# AVR-Timer_smd.net
KiCad netlist of a schematic drawn in EAGLE
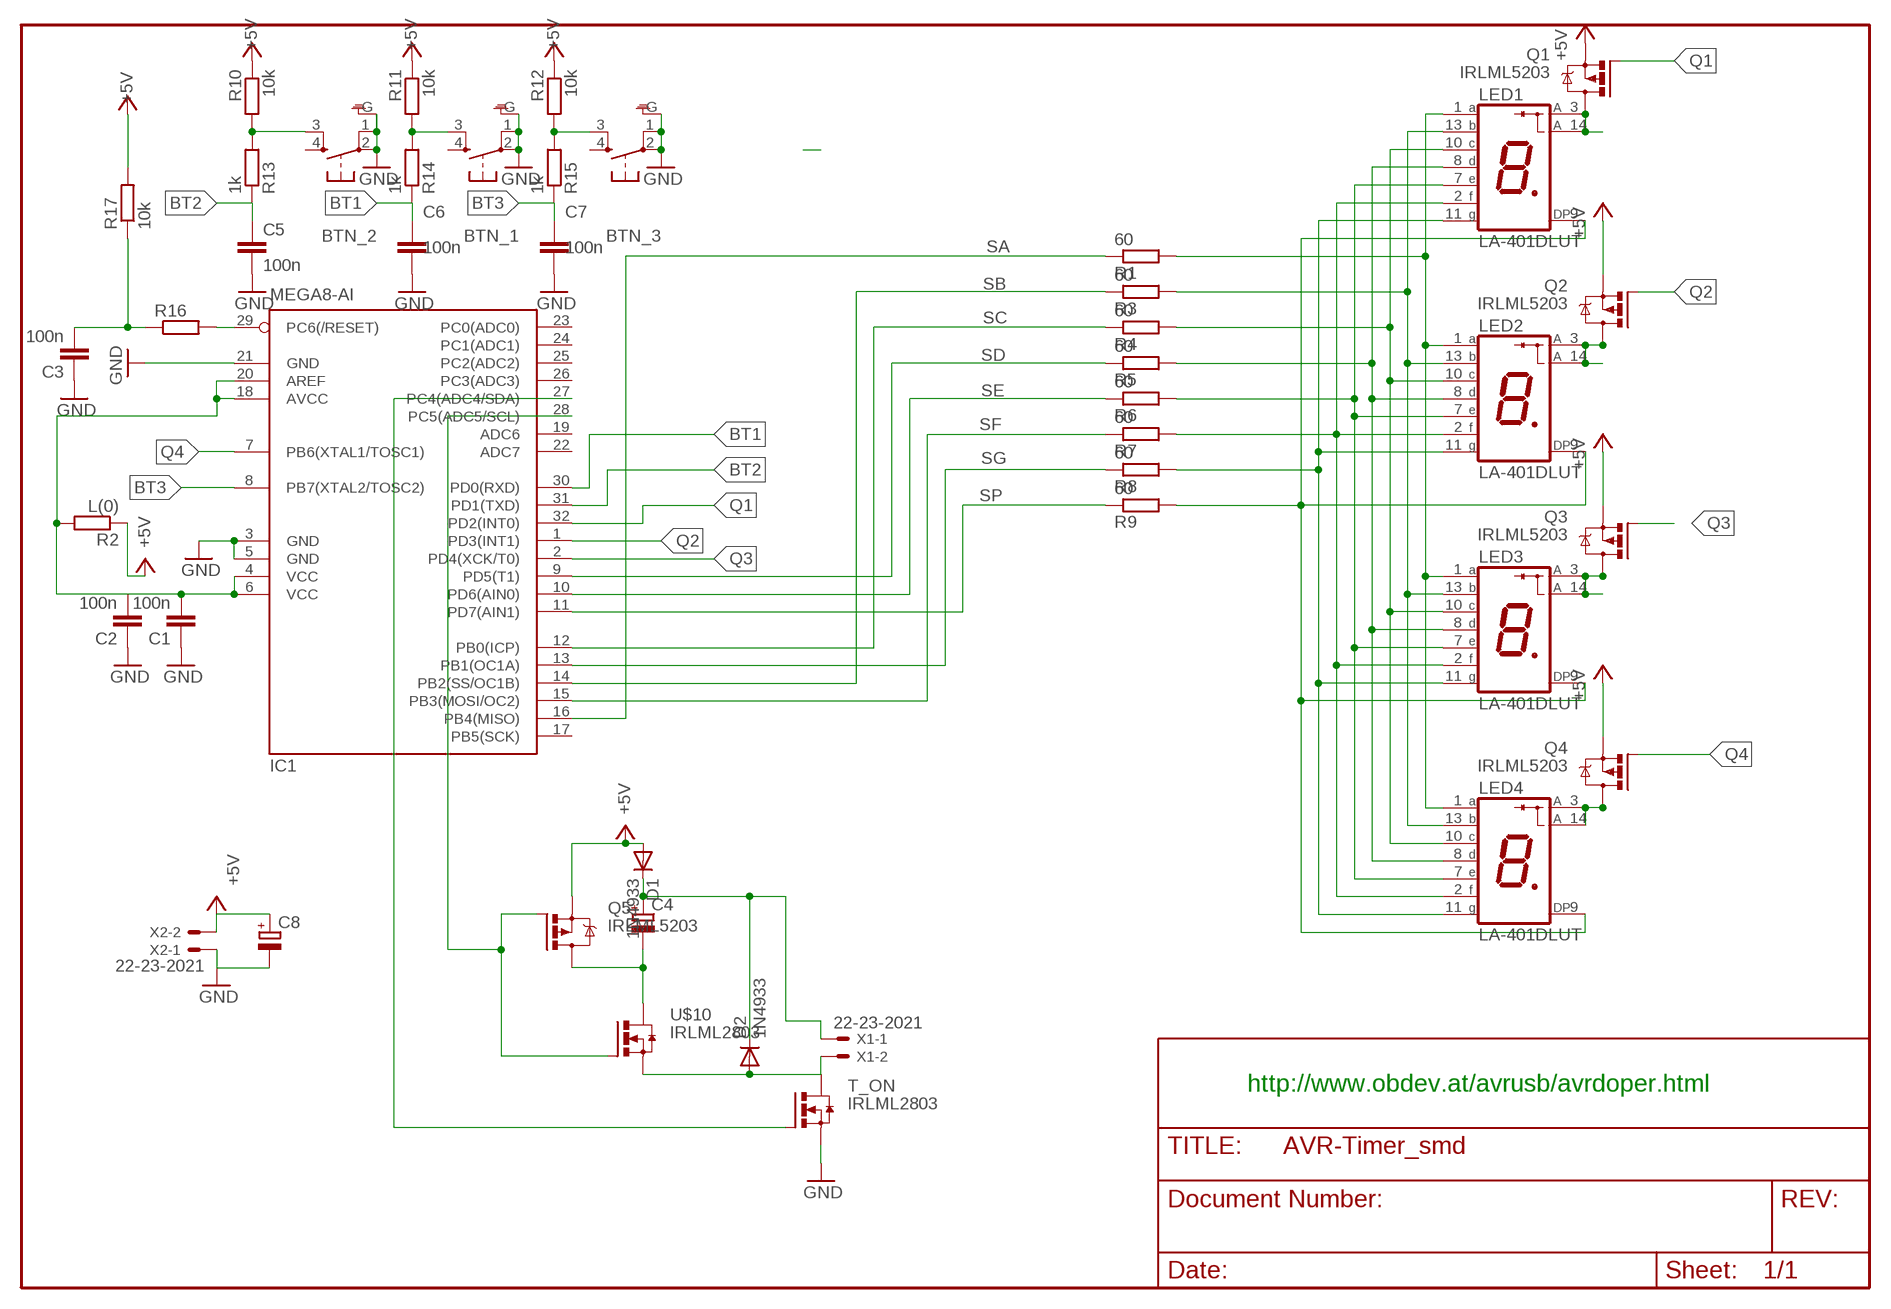
[diagram p0: schematic, sheet 1]

(export (version "E")
  (design (tool "Eeschema 10.0.6"))
  (components
    (comp (ref "BTN_1")
      (value "10-XXG")
      (footprint "eagle-import:B3F-10XXG")
      (libsource (lib "eagle-import") (part "10-XXG"))
    )
    (comp (ref "BTN_2")
      (value "10-XXG")
      (footprint "eagle-import:B3F-10XXG")
      (libsource (lib "eagle-import") (part "10-XXG"))
    )
    (comp (ref "BTN_3")
      (value "10-XXG")
      (footprint "eagle-import:B3F-10XXG")
      (libsource (lib "eagle-import") (part "10-XXG"))
    )
    (comp (ref "C1")
      (value "100n")
      (footprint "eagle-import:C0805K")
      (libsource (lib "eagle-import") (part "C-EUC0805K"))
    )
    (comp (ref "C2")
      (value "100n")
      (footprint "eagle-import:C0805K")
      (libsource (lib "eagle-import") (part "C-EUC0805K"))
    )
    (comp (ref "C3")
      (value "100n")
      (footprint "eagle-import:C0805K")
      (libsource (lib "eagle-import") (part "C-EUC0805K"))
    )
    (comp (ref "C4")
      (value "CPOL-EUE5-8.5")
      (footprint "eagle-import:E5-8,5")
      (libsource (lib "eagle-import") (part "CPOL-EUE5-8.5"))
    )
    (comp (ref "C5")
      (value "100n")
      (footprint "eagle-import:C0805K")
      (libsource (lib "eagle-import") (part "C-EUC0805K"))
    )
    (comp (ref "C6")
      (value "100n")
      (footprint "eagle-import:C0805K")
      (libsource (lib "eagle-import") (part "C-EUC0805K"))
    )
    (comp (ref "C7")
      (value "100n")
      (footprint "eagle-import:C0805K")
      (libsource (lib "eagle-import") (part "C-EUC0805K"))
    )
    (comp (ref "C8")
      (value "CPOL-EUE5-8.5")
      (footprint "eagle-import:E5-8,5")
      (libsource (lib "eagle-import") (part "CPOL-EUE5-8.5"))
    )
    (comp (ref "D1")
      (value "1N4933")
      (footprint "eagle-import:DO41-10")
      (libsource (lib "eagle-import") (part "1N4933"))
    )
    (comp (ref "D2")
      (value "1N4933")
      (footprint "eagle-import:DO41-10")
      (libsource (lib "eagle-import") (part "1N4933"))
    )
    (comp (ref "IC1")
      (value "MEGA8-AI")
      (footprint "eagle-import:TQFP32-08")
      (libsource (lib "eagle-import") (part "MEGA8-AI"))
    )
    (comp (ref "LED1")
      (value "LA-401DLUT")
      (footprint "eagle-import:MY_LUT")
      (libsource (lib "eagle-import") (part "LA-401DLUT"))
    )
    (comp (ref "LED2")
      (value "LA-401DLUT")
      (footprint "eagle-import:MY_LUT")
      (libsource (lib "eagle-import") (part "LA-401DLUT"))
    )
    (comp (ref "LED3")
      (value "LA-401DLUT")
      (footprint "eagle-import:MY_LUT")
      (libsource (lib "eagle-import") (part "LA-401DLUT"))
    )
    (comp (ref "LED4")
      (value "LA-401DLUT")
      (footprint "eagle-import:MY_LUT")
      (libsource (lib "eagle-import") (part "LA-401DLUT"))
    )
    (comp (ref "Q1")
      (value "IRLML5203")
      (footprint "eagle-import:MICRO3")
      (libsource (lib "eagle-import") (part "IRLML5203"))
    )
    (comp (ref "Q2")
      (value "IRLML5203")
      (footprint "eagle-import:MICRO3")
      (libsource (lib "eagle-import") (part "IRLML5203"))
    )
    (comp (ref "Q3")
      (value "IRLML5203")
      (footprint "eagle-import:MICRO3")
      (libsource (lib "eagle-import") (part "IRLML5203"))
    )
    (comp (ref "Q4")
      (value "IRLML5203")
      (footprint "eagle-import:MICRO3")
      (libsource (lib "eagle-import") (part "IRLML5203"))
    )
    (comp (ref "Q5")
      (value "IRLML5203")
      (footprint "eagle-import:MICRO3")
      (libsource (lib "eagle-import") (part "IRLML5203"))
    )
    (comp (ref "R1")
      (value "60")
      (footprint "eagle-import:M0805")
      (libsource (lib "eagle-import") (part "R-EU_M0805"))
    )
    (comp (ref "R2")
      (value "L(0)")
      (footprint "eagle-import:M1206")
      (libsource (lib "eagle-import") (part "R-EU_M1206"))
    )
    (comp (ref "R3")
      (value "60")
      (footprint "eagle-import:M0805")
      (libsource (lib "eagle-import") (part "R-EU_M0805"))
    )
    (comp (ref "R4")
      (value "60")
      (footprint "eagle-import:M0805")
      (libsource (lib "eagle-import") (part "R-EU_M0805"))
    )
    (comp (ref "R5")
      (value "60")
      (footprint "eagle-import:M0805")
      (libsource (lib "eagle-import") (part "R-EU_M0805"))
    )
    (comp (ref "R6")
      (value "60")
      (footprint "eagle-import:M0805")
      (libsource (lib "eagle-import") (part "R-EU_M0805"))
    )
    (comp (ref "R7")
      (value "60")
      (footprint "eagle-import:M0805")
      (libsource (lib "eagle-import") (part "R-EU_M0805"))
    )
    (comp (ref "R8")
      (value "60")
      (footprint "eagle-import:M0805")
      (libsource (lib "eagle-import") (part "R-EU_M0805"))
    )
    (comp (ref "R9")
      (value "60")
      (footprint "eagle-import:M0805")
      (libsource (lib "eagle-import") (part "R-EU_M0805"))
    )
    (comp (ref "R10")
      (value "10k")
      (footprint "eagle-import:M0805")
      (libsource (lib "eagle-import") (part "R-EU_M0805"))
    )
    (comp (ref "R11")
      (value "10k")
      (footprint "eagle-import:M0805")
      (libsource (lib "eagle-import") (part "R-EU_M0805"))
    )
    (comp (ref "R12")
      (value "10k")
      (footprint "eagle-import:M0805")
      (libsource (lib "eagle-import") (part "R-EU_M0805"))
    )
    (comp (ref "R13")
      (value "1k")
      (footprint "eagle-import:M0805")
      (libsource (lib "eagle-import") (part "R-EU_M0805"))
    )
    (comp (ref "R14")
      (value "1k")
      (footprint "eagle-import:M0805")
      (libsource (lib "eagle-import") (part "R-EU_M0805"))
    )
    (comp (ref "R15")
      (value "1k")
      (footprint "eagle-import:M0805")
      (libsource (lib "eagle-import") (part "R-EU_M0805"))
    )
    (comp (ref "R16")
      (value "R-EU_M1206")
      (footprint "eagle-import:M1206")
      (libsource (lib "eagle-import") (part "R-EU_M1206"))
    )
    (comp (ref "R17")
      (value "10k")
      (footprint "eagle-import:M1206")
      (libsource (lib "eagle-import") (part "R-EU_M1206"))
    )
    (comp (ref "T_ON")
      (value "IRLML2803")
      (footprint "eagle-import:SUPER-SOT3")
      (libsource (lib "eagle-import") (part "IRLML2803"))
    )
    (comp (ref "U$10")
      (value "IRLML2803")
      (footprint "eagle-import:SUPER-SOT3")
      (libsource (lib "eagle-import") (part "IRLML2803"))
    )
    (comp (ref "X1")
      (value "22-23-2021")
      (footprint "eagle-import:22-23-2021")
      (fields (field (name "MF") "MOLEX"))
      (libsource (lib "eagle-import") (part "22-23-2021"))
    )
    (comp (ref "X2")
      (value "22-23-2021")
      (footprint "eagle-import:22-23-2021")
      (fields
        (field (name "MF") "MOLEX")
        (field (name "MF_1") "MOLEX")
        (field (name "MPN") "22-23-2021")
        (field (name "OC_FARNELL") "1462926")
        (field (name "OC_NEWARK") "25C3832")
      )
      (libsource (lib "eagle-import") (part "22-23-2021"))
    )
  )
  (nets
    (net (code "1") (name "+5V") (class "Default")
      (node (ref "C8") (pin "+") (pinfunction "+_+") (pintype "passive"))
      (node (ref "D1") (pin "A") (pinfunction "A_A") (pintype "passive"))
      (node (ref "Q1") (pin "2") (pinfunction "S_2") (pintype "passive"))
      (node (ref "Q2") (pin "2") (pinfunction "S_2") (pintype "passive"))
      (node (ref "Q3") (pin "2") (pinfunction "S_2") (pintype "passive"))
      (node (ref "Q4") (pin "2") (pinfunction "S_2") (pintype "passive"))
      (node (ref "Q5") (pin "2") (pinfunction "S_2") (pintype "passive"))
      (node (ref "R10") (pin "1") (pinfunction "1_1") (pintype "passive"))
      (node (ref "R11") (pin "1") (pinfunction "1_1") (pintype "passive"))
      (node (ref "R12") (pin "1") (pinfunction "1_1") (pintype "passive"))
      (node (ref "R17") (pin "2") (pinfunction "2_2") (pintype "passive"))
      (node (ref "R2") (pin "1") (pinfunction "1_1") (pintype "passive"))
      (node (ref "X2") (pin "2") (pinfunction "S_2") (pintype "passive"))
    )
    (net (code "2") (name "/SA") (class "Default")
      (node (ref "IC1") (pin "16") (pinfunction "PB4(MISO)_16") (pintype "bidirectional"))
      (node (ref "R1") (pin "1") (pinfunction "1_1") (pintype "passive"))
    )
    (net (code "3") (name "/SB") (class "Default")
      (node (ref "IC1") (pin "14") (pinfunction "PB2(SS/OC1B)_14") (pintype "bidirectional"))
      (node (ref "R3") (pin "1") (pinfunction "1_1") (pintype "passive"))
    )
    (net (code "4") (name "/SC") (class "Default")
      (node (ref "IC1") (pin "12") (pinfunction "PB0(ICP)_12") (pintype "bidirectional"))
      (node (ref "R4") (pin "1") (pinfunction "1_1") (pintype "passive"))
    )
    (net (code "5") (name "/SD") (class "Default")
      (node (ref "IC1") (pin "9") (pinfunction "PD5(T1)_9") (pintype "bidirectional"))
      (node (ref "R5") (pin "1") (pinfunction "1_1") (pintype "passive"))
    )
    (net (code "6") (name "/SE") (class "Default")
      (node (ref "IC1") (pin "10") (pinfunction "PD6(AIN0)_10") (pintype "bidirectional"))
      (node (ref "R6") (pin "1") (pinfunction "1_1") (pintype "passive"))
    )
    (net (code "7") (name "/SF") (class "Default")
      (node (ref "IC1") (pin "15") (pinfunction "PB3(MOSI/OC2)_15") (pintype "bidirectional"))
      (node (ref "R7") (pin "1") (pinfunction "1_1") (pintype "passive"))
    )
    (net (code "8") (name "/SG") (class "Default")
      (node (ref "IC1") (pin "13") (pinfunction "PB1(OC1A)_13") (pintype "bidirectional"))
      (node (ref "R8") (pin "1") (pinfunction "1_1") (pintype "passive"))
    )
    (net (code "9") (name "/SP") (class "Default")
      (node (ref "IC1") (pin "11") (pinfunction "PD7(AIN1)_11") (pintype "bidirectional"))
      (node (ref "R9") (pin "1") (pinfunction "1_1") (pintype "passive"))
    )
    (net (code "10") (name "BT1") (class "Default")
      (node (ref "C6") (pin "1") (pinfunction "1_1") (pintype "passive"))
      (node (ref "IC1") (pin "30") (pinfunction "PD0(RXD)_30") (pintype "bidirectional"))
      (node (ref "R14") (pin "1") (pinfunction "1_1") (pintype "passive"))
    )
    (net (code "11") (name "BT2") (class "Default")
      (node (ref "C5") (pin "1") (pinfunction "1_1") (pintype "passive"))
      (node (ref "IC1") (pin "31") (pinfunction "PD1(TXD)_31") (pintype "bidirectional"))
      (node (ref "R13") (pin "1") (pinfunction "1_1") (pintype "passive"))
    )
    (net (code "12") (name "BT3") (class "Default")
      (node (ref "C7") (pin "1") (pinfunction "1_1") (pintype "passive"))
      (node (ref "IC1") (pin "8") (pinfunction "PB7(XTAL2/TOSC2)_8") (pintype "bidirectional"))
      (node (ref "R15") (pin "1") (pinfunction "1_1") (pintype "passive"))
    )
    (net (code "13") (name "GND") (class "Default")
      (node (ref "BTN_1") (pin "1") (pinfunction "P1_1") (pintype "passive"))
      (node (ref "BTN_1") (pin "2") (pinfunction "P_2") (pintype "passive"))
      (node (ref "BTN_1") (pin "G") (pinfunction "GND_G") (pintype "power_in"))
      (node (ref "BTN_2") (pin "1") (pinfunction "P1_1") (pintype "passive"))
      (node (ref "BTN_2") (pin "2") (pinfunction "P_2") (pintype "passive"))
      (node (ref "BTN_2") (pin "G") (pinfunction "GND_G") (pintype "power_in"))
      (node (ref "BTN_3") (pin "1") (pinfunction "P1_1") (pintype "passive"))
      (node (ref "BTN_3") (pin "2") (pinfunction "P_2") (pintype "passive"))
      (node (ref "BTN_3") (pin "G") (pinfunction "GND_G") (pintype "power_in"))
      (node (ref "C1") (pin "1") (pinfunction "1_1") (pintype "passive"))
      (node (ref "C2") (pin "1") (pinfunction "1_1") (pintype "passive"))
      (node (ref "C3") (pin "1") (pinfunction "1_1") (pintype "passive"))
      (node (ref "C5") (pin "2") (pinfunction "2_2") (pintype "passive"))
      (node (ref "C6") (pin "2") (pinfunction "2_2") (pintype "passive"))
      (node (ref "C7") (pin "2") (pinfunction "2_2") (pintype "passive"))
      (node (ref "C8") (pin "-") (pinfunction "-_-") (pintype "passive"))
      (node (ref "IC1") (pin "21") (pinfunction "GND_21") (pintype "power_in"))
      (node (ref "IC1") (pin "3") (pinfunction "GND_3") (pintype "power_in"))
      (node (ref "IC1") (pin "5") (pinfunction "GND_5") (pintype "power_in"))
      (node (ref "T_ON") (pin "2") (pinfunction "S_2") (pintype "passive"))
      (node (ref "X2") (pin "1") (pinfunction "S_1") (pintype "passive"))
    )
    (net (code "14") (name "Net-(BTN_1-S1)") (class "Default")
      (node (ref "BTN_1") (pin "3") (pinfunction "S1_3") (pintype "passive"))
      (node (ref "R11") (pin "2") (pinfunction "2_2") (pintype "passive"))
      (node (ref "R14") (pin "2") (pinfunction "2_2") (pintype "passive"))
    )
    (net (code "15") (name "Net-(BTN_2-S1)") (class "Default")
      (node (ref "BTN_2") (pin "3") (pinfunction "S1_3") (pintype "passive"))
      (node (ref "R10") (pin "2") (pinfunction "2_2") (pintype "passive"))
      (node (ref "R13") (pin "2") (pinfunction "2_2") (pintype "passive"))
    )
    (net (code "16") (name "Net-(BTN_3-S1)") (class "Default")
      (node (ref "BTN_3") (pin "3") (pinfunction "S1_3") (pintype "passive"))
      (node (ref "R12") (pin "2") (pinfunction "2_2") (pintype "passive"))
      (node (ref "R15") (pin "2") (pinfunction "2_2") (pintype "passive"))
    )
    (net (code "17") (name "Net-(C3-Pad2)") (class "Default")
      (node (ref "C3") (pin "2") (pinfunction "2_2") (pintype "passive"))
      (node (ref "R16") (pin "1") (pinfunction "1_1") (pintype "passive"))
      (node (ref "R17") (pin "1") (pinfunction "1_1") (pintype "passive"))
    )
    (net (code "18") (name "Net-(IC1-AREF)") (class "Default")
      (node (ref "C1") (pin "2") (pinfunction "2_2") (pintype "passive"))
      (node (ref "C2") (pin "2") (pinfunction "2_2") (pintype "passive"))
      (node (ref "IC1") (pin "18") (pinfunction "AVCC_18") (pintype "power_in"))
      (node (ref "IC1") (pin "20") (pinfunction "AREF_20") (pintype "passive"))
      (node (ref "IC1") (pin "4") (pinfunction "VCC_4") (pintype "power_in"))
      (node (ref "IC1") (pin "6") (pinfunction "VCC_6") (pintype "power_in"))
      (node (ref "R2") (pin "2") (pinfunction "2_2") (pintype "passive"))
    )
    (net (code "19") (name "Net-(IC1-PC4(ADC4{slash}SDA))") (class "Default")
      (node (ref "IC1") (pin "27") (pinfunction "PC4(ADC4/SDA)_27") (pintype "bidirectional"))
      (node (ref "T_ON") (pin "1") (pinfunction "G_1") (pintype "passive"))
    )
    (net (code "20") (name "Net-(IC1-PC5(ADC5{slash}SCL))") (class "Default")
      (node (ref "IC1") (pin "28") (pinfunction "PC5(ADC5/SCL)_28") (pintype "bidirectional"))
      (node (ref "Q5") (pin "1") (pinfunction "G_1") (pintype "passive"))
      (node (ref "U$10") (pin "1") (pinfunction "G_1") (pintype "passive"))
    )
    (net (code "21") (name "Net-(IC1-PC6({slash}RESET))") (class "Default")
      (node (ref "IC1") (pin "29") (pinfunction "PC6(/RESET)_29") (pintype "bidirectional"))
      (node (ref "R16") (pin "2") (pinfunction "2_2") (pintype "passive"))
    )
    (net (code "22") (name "Net-(LED1-A-Pad1)") (class "Default")
      (node (ref "LED1") (pin "1") (pinfunction "A_1") (pintype "passive"))
      (node (ref "LED2") (pin "1") (pinfunction "A_1") (pintype "passive"))
      (node (ref "LED3") (pin "1") (pinfunction "A_1") (pintype "passive"))
      (node (ref "LED4") (pin "1") (pinfunction "A_1") (pintype "passive"))
      (node (ref "R1") (pin "2") (pinfunction "2_2") (pintype "passive"))
    )
    (net (code "23") (name "Net-(LED1-B)") (class "Default")
      (node (ref "LED1") (pin "13") (pinfunction "B_13") (pintype "passive"))
      (node (ref "LED2") (pin "13") (pinfunction "B_13") (pintype "passive"))
      (node (ref "LED3") (pin "13") (pinfunction "B_13") (pintype "passive"))
      (node (ref "LED4") (pin "13") (pinfunction "B_13") (pintype "passive"))
      (node (ref "R3") (pin "2") (pinfunction "2_2") (pintype "passive"))
    )
    (net (code "24") (name "Net-(LED1-C)") (class "Default")
      (node (ref "LED1") (pin "10") (pinfunction "C_10") (pintype "passive"))
      (node (ref "LED2") (pin "10") (pinfunction "C_10") (pintype "passive"))
      (node (ref "LED3") (pin "10") (pinfunction "C_10") (pintype "passive"))
      (node (ref "LED4") (pin "10") (pinfunction "C_10") (pintype "passive"))
      (node (ref "R4") (pin "2") (pinfunction "2_2") (pintype "passive"))
    )
    (net (code "25") (name "Net-(LED1-D)") (class "Default")
      (node (ref "LED1") (pin "8") (pinfunction "D_8") (pintype "passive"))
      (node (ref "LED2") (pin "8") (pinfunction "D_8") (pintype "passive"))
      (node (ref "LED3") (pin "8") (pinfunction "D_8") (pintype "passive"))
      (node (ref "LED4") (pin "8") (pinfunction "D_8") (pintype "passive"))
      (node (ref "R5") (pin "2") (pinfunction "2_2") (pintype "passive"))
    )
    (net (code "26") (name "Net-(LED1-DP)") (class "Default")
      (node (ref "LED1") (pin "9") (pinfunction "DP_9") (pintype "passive"))
      (node (ref "LED2") (pin "9") (pinfunction "DP_9") (pintype "passive"))
      (node (ref "LED3") (pin "9") (pinfunction "DP_9") (pintype "passive"))
      (node (ref "LED4") (pin "9") (pinfunction "DP_9") (pintype "passive"))
      (node (ref "R9") (pin "2") (pinfunction "2_2") (pintype "passive"))
    )
    (net (code "27") (name "Net-(LED1-E)") (class "Default")
      (node (ref "LED1") (pin "7") (pinfunction "E_7") (pintype "passive"))
      (node (ref "LED2") (pin "7") (pinfunction "E_7") (pintype "passive"))
      (node (ref "LED3") (pin "7") (pinfunction "E_7") (pintype "passive"))
      (node (ref "LED4") (pin "7") (pinfunction "E_7") (pintype "passive"))
      (node (ref "R6") (pin "2") (pinfunction "2_2") (pintype "passive"))
    )
    (net (code "28") (name "Net-(LED1-F)") (class "Default")
      (node (ref "LED1") (pin "2") (pinfunction "F_2") (pintype "passive"))
      (node (ref "LED2") (pin "2") (pinfunction "F_2") (pintype "passive"))
      (node (ref "LED3") (pin "2") (pinfunction "F_2") (pintype "passive"))
      (node (ref "LED4") (pin "2") (pinfunction "F_2") (pintype "passive"))
      (node (ref "R7") (pin "2") (pinfunction "2_2") (pintype "passive"))
    )
    (net (code "29") (name "Net-(LED1-G)") (class "Default")
      (node (ref "LED1") (pin "11") (pinfunction "G_11") (pintype "passive"))
      (node (ref "LED2") (pin "11") (pinfunction "G_11") (pintype "passive"))
      (node (ref "LED3") (pin "11") (pinfunction "G_11") (pintype "passive"))
      (node (ref "LED4") (pin "11") (pinfunction "G_11") (pintype "passive"))
      (node (ref "R8") (pin "2") (pinfunction "2_2") (pintype "passive"))
    )
    (net (code "30") (name "Net-(Q1-D)") (class "Default")
      (node (ref "LED1") (pin "14") (pinfunction "A_14") (pintype "passive"))
      (node (ref "LED1") (pin "3") (pinfunction "A_3") (pintype "passive"))
      (node (ref "Q1") (pin "3") (pinfunction "D_3") (pintype "passive"))
    )
    (net (code "31") (name "Net-(Q2-D)") (class "Default")
      (node (ref "LED2") (pin "14") (pinfunction "A_14") (pintype "passive"))
      (node (ref "LED2") (pin "3") (pinfunction "A_3") (pintype "passive"))
      (node (ref "Q2") (pin "3") (pinfunction "D_3") (pintype "passive"))
    )
    (net (code "32") (name "Net-(Q3-D)") (class "Default")
      (node (ref "LED3") (pin "14") (pinfunction "A_14") (pintype "passive"))
      (node (ref "LED3") (pin "3") (pinfunction "A_3") (pintype "passive"))
      (node (ref "Q3") (pin "3") (pinfunction "D_3") (pintype "passive"))
    )
    (net (code "33") (name "Net-(Q4-D)") (class "Default")
      (node (ref "LED4") (pin "14") (pinfunction "A_14") (pintype "passive"))
      (node (ref "LED4") (pin "3") (pinfunction "A_3") (pintype "passive"))
      (node (ref "Q4") (pin "3") (pinfunction "D_3") (pintype "passive"))
    )
    (net (code "34") (name "Net-(Q5-D)") (class "Default")
      (node (ref "C4") (pin "-") (pinfunction "-_-") (pintype "passive"))
      (node (ref "Q5") (pin "3") (pinfunction "D_3") (pintype "passive"))
      (node (ref "U$10") (pin "3") (pinfunction "D_3") (pintype "passive"))
    )
    (net (code "35") (name "Net-(T_ON-D)") (class "Default")
      (node (ref "D2") (pin "A") (pinfunction "A_A") (pintype "passive"))
      (node (ref "T_ON") (pin "3") (pinfunction "D_3") (pintype "passive"))
      (node (ref "U$10") (pin "2") (pinfunction "S_2") (pintype "passive"))
      (node (ref "X1") (pin "2") (pinfunction "S_2") (pintype "passive"))
    )
    (net (code "36") (name "Net-(X1A-S)") (class "Default")
      (node (ref "C4") (pin "+") (pinfunction "+_+") (pintype "passive"))
      (node (ref "D1") (pin "C") (pinfunction "C_C") (pintype "passive"))
      (node (ref "D2") (pin "C") (pinfunction "C_C") (pintype "passive"))
      (node (ref "X1") (pin "1") (pinfunction "S_1") (pintype "passive"))
    )
    (net (code "37") (name "Q1") (class "Default")
      (node (ref "IC1") (pin "32") (pinfunction "PD2(INT0)_32") (pintype "bidirectional"))
      (node (ref "Q1") (pin "1") (pinfunction "G_1") (pintype "passive"))
    )
    (net (code "38") (name "Q2") (class "Default")
      (node (ref "IC1") (pin "1") (pinfunction "PD3(INT1)_1") (pintype "bidirectional"))
      (node (ref "Q2") (pin "1") (pinfunction "G_1") (pintype "passive"))
    )
    (net (code "39") (name "Q3") (class "Default")
      (node (ref "IC1") (pin "2") (pinfunction "PD4(XCK/T0)_2") (pintype "bidirectional"))
      (node (ref "Q3") (pin "1") (pinfunction "G_1") (pintype "passive"))
    )
    (net (code "40") (name "Q4") (class "Default")
      (node (ref "IC1") (pin "7") (pinfunction "PB6(XTAL1/TOSC1)_7") (pintype "bidirectional"))
      (node (ref "Q4") (pin "1") (pinfunction "G_1") (pintype "passive"))
    )
    (net (code "41") (name "unconnected-(BTN_1-S-Pad4)") (class "Default")
      (node (ref "BTN_1") (pin "4") (pinfunction "S_4") (pintype "passive"))
    )
    (net (code "42") (name "unconnected-(BTN_2-S-Pad4)") (class "Default")
      (node (ref "BTN_2") (pin "4") (pinfunction "S_4") (pintype "passive"))
    )
    (net (code "43") (name "unconnected-(BTN_3-S-Pad4)") (class "Default")
      (node (ref "BTN_3") (pin "4") (pinfunction "S_4") (pintype "passive"))
    )
    (net (code "44") (name "unconnected-(IC1-ADC6-Pad19)") (class "Default")
      (node (ref "IC1") (pin "19") (pinfunction "ADC6_19") (pintype "bidirectional"))
    )
    (net (code "45") (name "unconnected-(IC1-ADC7-Pad22)") (class "Default")
      (node (ref "IC1") (pin "22") (pinfunction "ADC7_22") (pintype "bidirectional"))
    )
    (net (code "46") (name "unconnected-(IC1-PB5(SCK)-Pad17)") (class "Default")
      (node (ref "IC1") (pin "17") (pinfunction "PB5(SCK)_17") (pintype "bidirectional"))
    )
    (net (code "47") (name "unconnected-(IC1-PC0(ADC0)-Pad23)") (class "Default")
      (node (ref "IC1") (pin "23") (pinfunction "PC0(ADC0)_23") (pintype "bidirectional"))
    )
    (net (code "48") (name "unconnected-(IC1-PC1(ADC1)-Pad24)") (class "Default")
      (node (ref "IC1") (pin "24") (pinfunction "PC1(ADC1)_24") (pintype "bidirectional"))
    )
    (net (code "49") (name "unconnected-(IC1-PC2(ADC2)-Pad25)") (class "Default")
      (node (ref "IC1") (pin "25") (pinfunction "PC2(ADC2)_25") (pintype "bidirectional"))
    )
    (net (code "50") (name "unconnected-(IC1-PC3(ADC3)-Pad26)") (class "Default")
      (node (ref "IC1") (pin "26") (pinfunction "PC3(ADC3)_26") (pintype "bidirectional"))
    )
  )
)
